# sra_board_2020.net
KiCad netlist of a schematic drawn in EAGLE
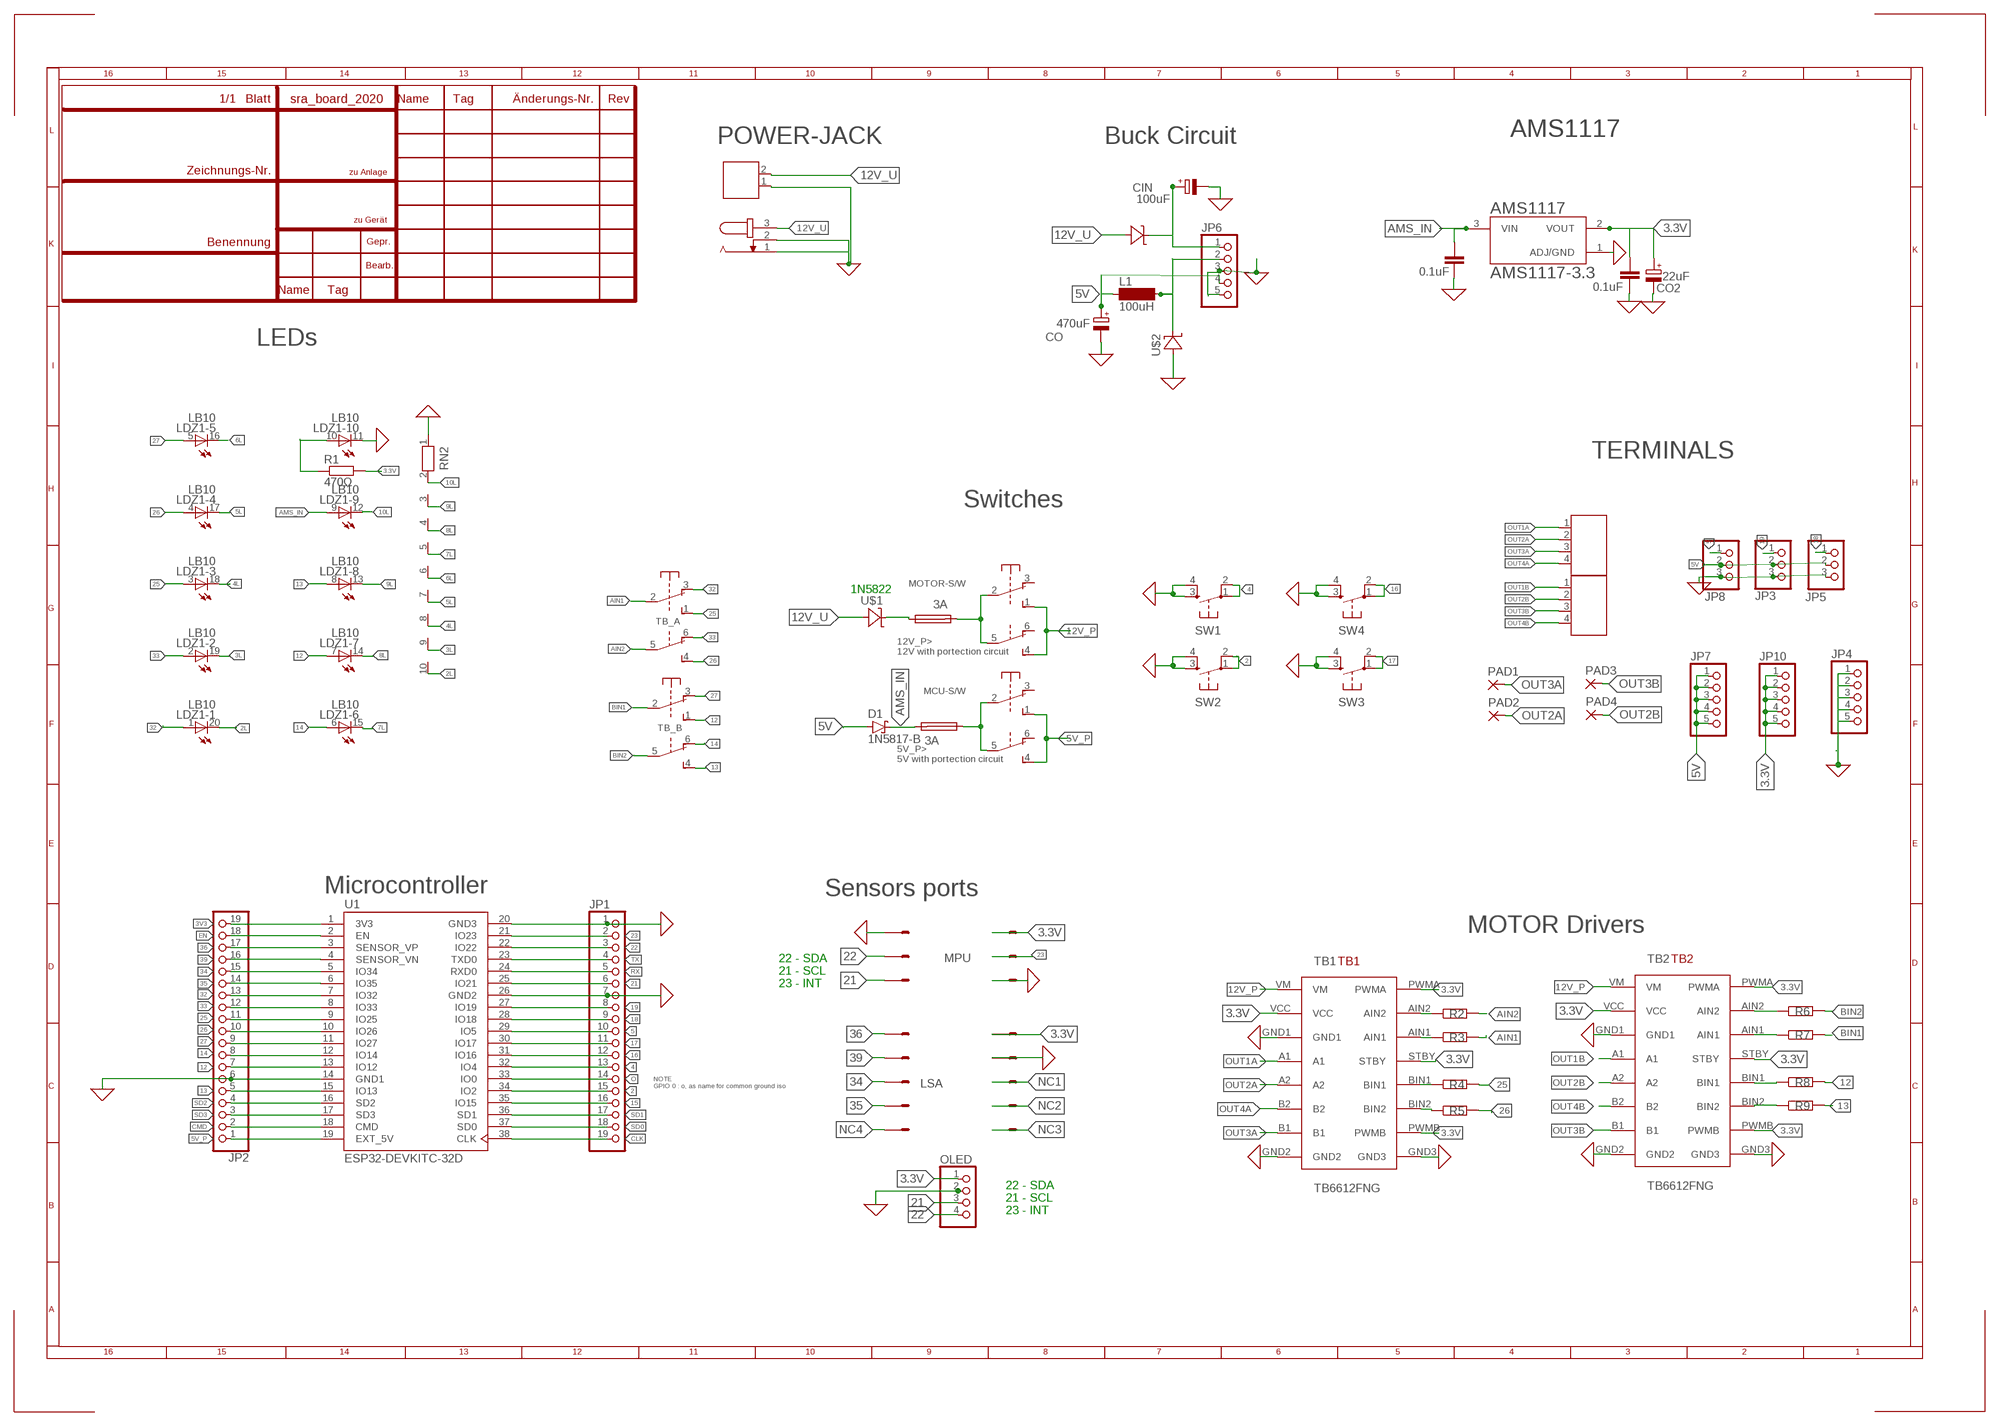
[diagram p0: schematic, sheet 1]

(export (version "E")
  (design (tool "Eeschema 10.0.6"))
  (components
    (comp (ref "12V")
      (value "691131710002")
      (footprint "eagle-import:691131710002")
      (libsource (lib "eagle-import") (part "691131710002"))
    )
    (comp (ref "AMS1117")
      (value "AMS1117-3.3")
      (footprint "eagle-import:SOT229P700X180-4N")
      (fields (field (name "MF") "Advanced Monolithic Systems"))
      (libsource (lib "eagle-import") (part "AMS1117-3.3"))
    )
    (comp (ref "CIN")
      (value "100uF")
      (footprint "eagle-import:E2,5-6")
      (libsource (lib "eagle-import") (part "CPOL-EUE2.5-6"))
    )
    (comp (ref "CIN1")
      (value "0.1uF")
      (footprint "eagle-import:C5B2.5")
      (libsource (lib "eagle-import") (part "C5/2.5"))
    )
    (comp (ref "CO")
      (value "470uF")
      (footprint "eagle-import:E3,5-10")
      (libsource (lib "eagle-import") (part "CPOL-EUE3.5-10"))
    )
    (comp (ref "CO1")
      (value "0.1uF")
      (footprint "eagle-import:C5B2.5")
      (libsource (lib "eagle-import") (part "C5/2.5"))
    )
    (comp (ref "CO2")
      (value "22uF")
      (footprint "eagle-import:E2,5-6")
      (libsource (lib "eagle-import") (part "CPOL-EUE2.5-6"))
    )
    (comp (ref "D1")
      (value "1N5817-B")
      (footprint "eagle-import:DO41-7.6")
      (libsource (lib "eagle-import") (part "1N5817-B"))
    )
    (comp (ref "F2")
      (value "3A")
      (footprint "eagle-import:SH25")
      (fields (field (name "MF") "SCHURTER") (field (name "MPN") "0031.8211"))
      (libsource (lib "eagle-import") (part "SH25"))
    )
    (comp (ref "F3")
      (value "3A")
      (footprint "eagle-import:SH25")
      (fields (field (name "MF") "SCHURTER") (field (name "MPN") "0031.8211"))
      (libsource (lib "eagle-import") (part "SH25"))
    )
    (comp (ref "J1")
      (value "691131710004")
      (footprint "eagle-import:691131710004")
      (libsource (lib "eagle-import") (part "691131710004"))
    )
    (comp (ref "J2")
      (value "691131710004")
      (footprint "eagle-import:691131710004")
      (libsource (lib "eagle-import") (part "691131710004"))
    )
    (comp (ref "JP1")
      (value "PINHD-1X19")
      (footprint "eagle-import:1X19")
      (libsource (lib "eagle-import") (part "PINHD-1X19"))
    )
    (comp (ref "JP2")
      (value "PINHD-1X19")
      (footprint "eagle-import:1X19")
      (libsource (lib "eagle-import") (part "PINHD-1X19"))
    )
    (comp (ref "JP3")
      (value "PINHD-1X3")
      (footprint "eagle-import:1X03")
      (libsource (lib "eagle-import") (part "PINHD-1X3"))
    )
    (comp (ref "JP4")
      (value "PINHD-1X5")
      (footprint "eagle-import:1X05")
      (libsource (lib "eagle-import") (part "pinhead_2_PINHD-1X5"))
    )
    (comp (ref "JP5")
      (value "PINHD-1X3")
      (footprint "eagle-import:1X03")
      (libsource (lib "eagle-import") (part "PINHD-1X3"))
    )
    (comp (ref "JP6")
      (value "PINHD-1X5")
      (footprint "eagle-import:1X05")
      (libsource (lib "eagle-import") (part "PINHD-1X5"))
    )
    (comp (ref "JP7")
      (value "PINHD-1X5")
      (footprint "eagle-import:1X05")
      (libsource (lib "eagle-import") (part "pinhead_2_PINHD-1X5"))
    )
    (comp (ref "JP8")
      (value "PINHD-1X3")
      (footprint "eagle-import:1X03")
      (libsource (lib "eagle-import") (part "PINHD-1X3"))
    )
    (comp (ref "JP10")
      (value "PINHD-1X5")
      (footprint "eagle-import:1X05")
      (libsource (lib "eagle-import") (part "pinhead_2_PINHD-1X5"))
    )
    (comp (ref "L1")
      (value "100uH")
      (footprint "eagle-import:SD12K100")
      (libsource (lib "eagle-import") (part "SD12K100"))
    )
    (comp (ref "LDZ1")
      (value "LB10")
      (footprint "eagle-import:LB10")
      (libsource (lib "eagle-import") (part "LB10"))
    )
    (comp (ref "LINE-SENSOR")
      (value "057-010-1")
      (footprint "eagle-import:057-010-1")
      (libsource (lib "eagle-import") (part "057-010-1"))
    )
    (comp (ref "MCU-S/W")
      (value "9077-2")
      (footprint "eagle-import:9077-2")
      (libsource (lib "eagle-import") (part "9077-2"))
    )
    (comp (ref "MOTOR-S/W")
      (value "9077-2")
      (footprint "eagle-import:9077-2")
      (libsource (lib "eagle-import") (part "9077-2"))
    )
    (comp (ref "OLED")
      (value "PINHD-1X4")
      (footprint "eagle-import:1X04")
      (libsource (lib "eagle-import") (part "PINHD-1X4"))
    )
    (comp (ref "PAD1")
      (value "SMD2")
      (footprint "eagle-import:SMD1,27-2,54")
      (libsource (lib "eagle-import") (part "SMD2"))
    )
    (comp (ref "PAD2")
      (value "SMD2")
      (footprint "eagle-import:SMD1,27-2,54")
      (libsource (lib "eagle-import") (part "SMD2"))
    )
    (comp (ref "PAD3")
      (value "SMD2")
      (footprint "eagle-import:SMD1,27-2,54")
      (libsource (lib "eagle-import") (part "SMD2"))
    )
    (comp (ref "PAD4")
      (value "SMD2")
      (footprint "eagle-import:SMD1,27-2,54")
      (libsource (lib "eagle-import") (part "SMD2"))
    )
    (comp (ref "POWER-JACK")
      (value "JACK-PLUG1")
      (footprint "eagle-import:SPC4078")
      (libsource (lib "eagle-import") (part "JACK-PLUG1"))
    )
    (comp (ref "R1")
      (value "470Ω")
      (footprint "eagle-import:0204_7")
      (libsource (lib "eagle-import") (part "R-EU_0204/7"))
    )
    (comp (ref "R2")
      (value "1KΩ")
      (footprint "eagle-import:0204_7")
      (libsource (lib "eagle-import") (part "R-EU_0204/7"))
    )
    (comp (ref "R3")
      (value "1KΩ")
      (footprint "eagle-import:0204_7")
      (libsource (lib "eagle-import") (part "R-EU_0204/7"))
    )
    (comp (ref "R4")
      (value "1KΩ")
      (footprint "eagle-import:0204_7")
      (libsource (lib "eagle-import") (part "R-EU_0204/7"))
    )
    (comp (ref "R5")
      (value "1KΩ")
      (footprint "eagle-import:0204_7")
      (libsource (lib "eagle-import") (part "R-EU_0204/7"))
    )
    (comp (ref "R6")
      (value "1KΩ")
      (footprint "eagle-import:0204_7")
      (libsource (lib "eagle-import") (part "R-EU_0204/7"))
    )
    (comp (ref "R7")
      (value "1KΩ")
      (footprint "eagle-import:0204_7")
      (libsource (lib "eagle-import") (part "R-EU_0204/7"))
    )
    (comp (ref "R8")
      (value "1KΩ")
      (footprint "eagle-import:0204_7")
      (libsource (lib "eagle-import") (part "R-EU_0204/7"))
    )
    (comp (ref "R9")
      (value "1KΩ")
      (footprint "eagle-import:0204_7")
      (libsource (lib "eagle-import") (part "R-EU_0204/7"))
    )
    (comp (ref "RN2")
      (value "RN09")
      (footprint "eagle-import:RN-10")
      (libsource (lib "eagle-import") (part "RN09"))
    )
    (comp (ref "SW1")
      (value "DTS-6")
      (footprint "eagle-import:DTS-6")
      (libsource (lib "eagle-import") (part "DTS-6"))
    )
    (comp (ref "SW2")
      (value "DTS-6")
      (footprint "eagle-import:DTS-6")
      (libsource (lib "eagle-import") (part "DTS-6"))
    )
    (comp (ref "SW3")
      (value "DTS-6")
      (footprint "eagle-import:DTS-6")
      (libsource (lib "eagle-import") (part "DTS-6"))
    )
    (comp (ref "SW4")
      (value "DTS-6")
      (footprint "eagle-import:DTS-6")
      (libsource (lib "eagle-import") (part "DTS-6"))
    )
    (comp (ref "TB1")
      (value "TB6612FNG")
      (footprint "eagle-import:TB6612FNG")
      (libsource (lib "eagle-import") (part "TB6612FNG"))
    )
    (comp (ref "TB2")
      (value "TB6612FNG")
      (footprint "eagle-import:TB6612FNG")
      (libsource (lib "eagle-import") (part "TB6612FNG"))
    )
    (comp (ref "TB_A")
      (value "9077-2")
      (footprint "eagle-import:9077-2")
      (libsource (lib "eagle-import") (part "9077-2"))
    )
    (comp (ref "TB_B")
      (value "9077-2")
      (footprint "eagle-import:9077-2")
      (libsource (lib "eagle-import") (part "9077-2"))
    )
    (comp (ref "U$1")
      (value "1N5399_SQUARE")
      (footprint "eagle-import:C2673")
      (libsource (lib "eagle-import") (part "1N5399_SQUARE"))
    )
    (comp (ref "U$2")
      (value "1N5399_SQUARE")
      (footprint "eagle-import:C2673")
      (libsource (lib "eagle-import") (part "1N5399_SQUARE"))
    )
    (comp (ref "U$3")
      (value "1N5399_ROUND")
      (footprint "eagle-import:D-10")
      (libsource (lib "eagle-import") (part "1N5399_ROUND"))
    )
    (comp (ref "U1")
      (value "ESP32-DEVKITC-32D")
      (footprint "eagle-import:MODULE_ESP32-DEVKITC-32D")
      (fields (field (name "MF") "Espressif Systems"))
      (libsource (lib "eagle-import") (part "ESP32-DEVKITC-32D"))
    )
    (comp (ref "X1")
      (value "057-006-1")
      (footprint "eagle-import:057-006-1")
      (libsource (lib "eagle-import") (part "057-006-1"))
    )
  )
  (nets
    (net (code "1") (name "2") (class "Default")
      (node (ref "JP1") (pin "15") (pinfunction "15_15") (pintype "passive"))
      (node (ref "SW2") (pin "1") (pinfunction "1_1") (pintype "passive"))
      (node (ref "SW2") (pin "2") (pinfunction "2_2") (pintype "passive"))
      (node (ref "U1") (pin "34") (pinfunction "IO2_34") (pintype "bidirectional"))
    )
    (net (code "2") (name "2L") (class "Default")
      (node (ref "LDZ1") (pin "20") (pinfunction "C_20") (pintype "passive"))
      (node (ref "RN2") (pin "10") (pinfunction "10_10") (pintype "passive"))
    )
    (net (code "3") (name "3.3V") (class "Default")
      (node (ref "AMS1117") (pin "2") (pinfunction "VOUT_2") (pintype "output"))
      (node (ref "CO1") (pin "2") (pinfunction "2_2") (pintype "passive"))
      (node (ref "CO2") (pin "+") (pinfunction "+_+") (pintype "passive"))
      (node (ref "JP10") (pin "1") (pinfunction "1_1") (pintype "passive"))
      (node (ref "JP10") (pin "2") (pinfunction "2_2") (pintype "passive"))
      (node (ref "JP10") (pin "3") (pinfunction "3_3") (pintype "passive"))
      (node (ref "JP10") (pin "4") (pinfunction "4_4") (pintype "passive"))
      (node (ref "JP10") (pin "5") (pinfunction "5_5") (pintype "passive"))
      (node (ref "LINE-SENSOR") (pin "2") (pinfunction "S_2") (pintype "passive"))
      (node (ref "OLED") (pin "1") (pinfunction "1_1") (pintype "passive"))
      (node (ref "R1") (pin "2") (pinfunction "2_2") (pintype "passive"))
      (node (ref "TB1") (pin "PWMA") (pinfunction "PWMA_PWMA") (pintype "bidirectional"))
      (node (ref "TB1") (pin "PWMB") (pinfunction "PWMB_PWMB") (pintype "bidirectional"))
      (node (ref "TB1") (pin "STBY") (pinfunction "STBY_STBY") (pintype "bidirectional"))
      (node (ref "TB1") (pin "VCC") (pinfunction "VCC_VCC") (pintype "bidirectional"))
      (node (ref "TB2") (pin "PWMA") (pinfunction "PWMA_PWMA") (pintype "bidirectional"))
      (node (ref "TB2") (pin "PWMB") (pinfunction "PWMB_PWMB") (pintype "bidirectional"))
      (node (ref "TB2") (pin "STBY") (pinfunction "STBY_STBY") (pintype "bidirectional"))
      (node (ref "TB2") (pin "VCC") (pinfunction "VCC_VCC") (pintype "bidirectional"))
      (node (ref "X1") (pin "2") (pinfunction "S_2") (pintype "passive"))
    )
    (net (code "4") (name "3L") (class "Default")
      (node (ref "LDZ1") (pin "19") (pinfunction "C_19") (pintype "passive"))
      (node (ref "RN2") (pin "9") (pinfunction "9_9") (pintype "passive"))
    )
    (net (code "5") (name "3V3") (class "Default")
      (node (ref "JP2") (pin "19") (pinfunction "19_19") (pintype "passive"))
      (node (ref "U1") (pin "1") (pinfunction "3V3_1") (pintype "power_in"))
    )
    (net (code "6") (name "4") (class "Default")
      (node (ref "JP1") (pin "13") (pinfunction "13_13") (pintype "passive"))
      (node (ref "SW1") (pin "1") (pinfunction "1_1") (pintype "passive"))
      (node (ref "SW1") (pin "2") (pinfunction "2_2") (pintype "passive"))
      (node (ref "U1") (pin "32") (pinfunction "IO4_32") (pintype "bidirectional"))
    )
    (net (code "7") (name "4L") (class "Default")
      (node (ref "LDZ1") (pin "18") (pinfunction "C_18") (pintype "passive"))
      (node (ref "RN2") (pin "8") (pinfunction "8_8") (pintype "passive"))
    )
    (net (code "8") (name "5") (class "Default")
      (node (ref "JP1") (pin "10") (pinfunction "10_10") (pintype "passive"))
      (node (ref "JP8") (pin "1") (pinfunction "1_1") (pintype "passive"))
      (node (ref "U1") (pin "29") (pinfunction "IO5_29") (pintype "bidirectional"))
    )
    (net (code "9") (name "5L") (class "Default")
      (node (ref "LDZ1") (pin "17") (pinfunction "C_17") (pintype "passive"))
      (node (ref "RN2") (pin "7") (pinfunction "7_7") (pintype "passive"))
    )
    (net (code "10") (name "5V") (class "Default")
      (node (ref "CO") (pin "+") (pinfunction "+_+") (pintype "passive"))
      (node (ref "D1") (pin "A") (pinfunction "A_A") (pintype "passive"))
      (node (ref "JP3") (pin "2") (pinfunction "2_2") (pintype "passive"))
      (node (ref "JP5") (pin "2") (pinfunction "2_2") (pintype "passive"))
      (node (ref "JP6") (pin "4") (pinfunction "4_4") (pintype "passive"))
      (node (ref "JP7") (pin "1") (pinfunction "1_1") (pintype "passive"))
      (node (ref "JP7") (pin "2") (pinfunction "2_2") (pintype "passive"))
      (node (ref "JP7") (pin "3") (pinfunction "3_3") (pintype "passive"))
      (node (ref "JP7") (pin "4") (pinfunction "4_4") (pintype "passive"))
      (node (ref "JP7") (pin "5") (pinfunction "5_5") (pintype "passive"))
      (node (ref "JP8") (pin "2") (pinfunction "2_2") (pintype "passive"))
      (node (ref "L1") (pin "1") (pinfunction "1_1") (pintype "passive"))
    )
    (net (code "11") (name "5V_P") (class "Default")
      (node (ref "JP2") (pin "1") (pinfunction "1_1") (pintype "passive"))
      (node (ref "MCU-S/W") (pin "1") (pinfunction "S_1") (pintype "passive"))
      (node (ref "MCU-S/W") (pin "4") (pinfunction "S_4") (pintype "passive"))
      (node (ref "U1") (pin "19") (pinfunction "EXT_5V_19") (pintype "power_in"))
    )
    (net (code "12") (name "6L") (class "Default")
      (node (ref "LDZ1") (pin "16") (pinfunction "C_16") (pintype "passive"))
      (node (ref "RN2") (pin "6") (pinfunction "6_6") (pintype "passive"))
    )
    (net (code "13") (name "7L") (class "Default")
      (node (ref "LDZ1") (pin "15") (pinfunction "C_15") (pintype "passive"))
      (node (ref "RN2") (pin "5") (pinfunction "5_5") (pintype "passive"))
    )
    (net (code "14") (name "8L") (class "Default")
      (node (ref "LDZ1") (pin "14") (pinfunction "C_14") (pintype "passive"))
      (node (ref "RN2") (pin "4") (pinfunction "4_4") (pintype "passive"))
    )
    (net (code "15") (name "9L") (class "Default")
      (node (ref "LDZ1") (pin "13") (pinfunction "C_13") (pintype "passive"))
      (node (ref "RN2") (pin "3") (pinfunction "3_3") (pintype "passive"))
    )
    (net (code "16") (name "10L") (class "Default")
      (node (ref "LDZ1") (pin "12") (pinfunction "C_12") (pintype "passive"))
      (node (ref "RN2") (pin "2") (pinfunction "2_2") (pintype "passive"))
    )
    (net (code "17") (name "12") (class "Default")
      (node (ref "JP2") (pin "7") (pinfunction "7_7") (pintype "passive"))
      (node (ref "LDZ1") (pin "7") (pinfunction "A_7") (pintype "passive"))
      (node (ref "R8") (pin "2") (pinfunction "2_2") (pintype "passive"))
      (node (ref "TB_B") (pin "1") (pinfunction "S_1") (pintype "passive"))
      (node (ref "U1") (pin "13") (pinfunction "IO12_13") (pintype "bidirectional"))
    )
    (net (code "18") (name "12V_P") (class "Default")
      (node (ref "MOTOR-S/W") (pin "1") (pinfunction "S_1") (pintype "passive"))
      (node (ref "MOTOR-S/W") (pin "4") (pinfunction "S_4") (pintype "passive"))
      (node (ref "TB1") (pin "VM") (pinfunction "VM_VM") (pintype "bidirectional"))
      (node (ref "TB2") (pin "VM") (pinfunction "VM_VM") (pintype "bidirectional"))
    )
    (net (code "19") (name "12V_U") (class "Default")
      (node (ref "12V") (pin "2") (pinfunction "2_2") (pintype "passive"))
      (node (ref "POWER-JACK") (pin "3") (pinfunction "3_3") (pintype "passive"))
      (node (ref "U$1") (pin "A") (pinfunction "A_A") (pintype "passive"))
      (node (ref "U$3") (pin "A") (pinfunction "A_A") (pintype "passive"))
    )
    (net (code "20") (name "13") (class "Default")
      (node (ref "JP2") (pin "5") (pinfunction "5_5") (pintype "passive"))
      (node (ref "LDZ1") (pin "8") (pinfunction "A_8") (pintype "passive"))
      (node (ref "R9") (pin "2") (pinfunction "2_2") (pintype "passive"))
      (node (ref "TB_B") (pin "4") (pinfunction "S_4") (pintype "passive"))
      (node (ref "U1") (pin "15") (pinfunction "IO13_15") (pintype "bidirectional"))
    )
    (net (code "21") (name "14") (class "Default")
      (node (ref "JP2") (pin "8") (pinfunction "8_8") (pintype "passive"))
      (node (ref "LDZ1") (pin "6") (pinfunction "A_6") (pintype "passive"))
      (node (ref "TB_B") (pin "6") (pinfunction "O_6") (pintype "passive"))
      (node (ref "U1") (pin "12") (pinfunction "IO14_12") (pintype "bidirectional"))
    )
    (net (code "22") (name "15") (class "Default")
      (node (ref "JP1") (pin "16") (pinfunction "16_16") (pintype "passive"))
      (node (ref "U1") (pin "35") (pinfunction "IO15_35") (pintype "bidirectional"))
    )
    (net (code "23") (name "16") (class "Default")
      (node (ref "JP1") (pin "12") (pinfunction "12_12") (pintype "passive"))
      (node (ref "SW4") (pin "1") (pinfunction "1_1") (pintype "passive"))
      (node (ref "SW4") (pin "2") (pinfunction "2_2") (pintype "passive"))
      (node (ref "U1") (pin "31") (pinfunction "IO16_31") (pintype "bidirectional"))
    )
    (net (code "24") (name "17") (class "Default")
      (node (ref "JP1") (pin "11") (pinfunction "11_11") (pintype "passive"))
      (node (ref "SW3") (pin "1") (pinfunction "1_1") (pintype "passive"))
      (node (ref "SW3") (pin "2") (pinfunction "2_2") (pintype "passive"))
      (node (ref "U1") (pin "30") (pinfunction "IO17_30") (pintype "bidirectional"))
    )
    (net (code "25") (name "18") (class "Default")
      (node (ref "JP1") (pin "9") (pinfunction "9_9") (pintype "passive"))
      (node (ref "JP5") (pin "1") (pinfunction "1_1") (pintype "passive"))
      (node (ref "U1") (pin "28") (pinfunction "IO18_28") (pintype "bidirectional"))
    )
    (net (code "26") (name "19") (class "Default")
      (node (ref "JP1") (pin "8") (pinfunction "8_8") (pintype "passive"))
      (node (ref "JP3") (pin "1") (pinfunction "1_1") (pintype "passive"))
      (node (ref "U1") (pin "27") (pinfunction "IO19_27") (pintype "bidirectional"))
    )
    (net (code "27") (name "21") (class "Default")
      (node (ref "JP1") (pin "6") (pinfunction "6_6") (pintype "passive"))
      (node (ref "OLED") (pin "3") (pinfunction "3_3") (pintype "passive"))
      (node (ref "U1") (pin "25") (pinfunction "IO21_25") (pintype "bidirectional"))
      (node (ref "X1") (pin "5") (pinfunction "S_5") (pintype "passive"))
    )
    (net (code "28") (name "22") (class "Default")
      (node (ref "JP1") (pin "3") (pinfunction "3_3") (pintype "passive"))
      (node (ref "OLED") (pin "4") (pinfunction "4_4") (pintype "passive"))
      (node (ref "U1") (pin "22") (pinfunction "IO22_22") (pintype "bidirectional"))
      (node (ref "X1") (pin "3") (pinfunction "S_3") (pintype "passive"))
    )
    (net (code "29") (name "23") (class "Default")
      (node (ref "JP1") (pin "2") (pinfunction "2_2") (pintype "passive"))
      (node (ref "U1") (pin "21") (pinfunction "IO23_21") (pintype "bidirectional"))
      (node (ref "X1") (pin "4") (pinfunction "S_4") (pintype "passive"))
    )
    (net (code "30") (name "25") (class "Default")
      (node (ref "JP2") (pin "11") (pinfunction "11_11") (pintype "passive"))
      (node (ref "LDZ1") (pin "3") (pinfunction "A_3") (pintype "passive"))
      (node (ref "R4") (pin "2") (pinfunction "2_2") (pintype "passive"))
      (node (ref "TB_A") (pin "1") (pinfunction "S_1") (pintype "passive"))
      (node (ref "U1") (pin "9") (pinfunction "IO25_9") (pintype "bidirectional"))
    )
    (net (code "31") (name "26") (class "Default")
      (node (ref "JP2") (pin "10") (pinfunction "10_10") (pintype "passive"))
      (node (ref "LDZ1") (pin "4") (pinfunction "A_4") (pintype "passive"))
      (node (ref "R5") (pin "2") (pinfunction "2_2") (pintype "passive"))
      (node (ref "TB_A") (pin "4") (pinfunction "S_4") (pintype "passive"))
      (node (ref "U1") (pin "10") (pinfunction "IO26_10") (pintype "bidirectional"))
    )
    (net (code "32") (name "27") (class "Default")
      (node (ref "JP2") (pin "9") (pinfunction "9_9") (pintype "passive"))
      (node (ref "LDZ1") (pin "5") (pinfunction "A_5") (pintype "passive"))
      (node (ref "TB_B") (pin "3") (pinfunction "O_3") (pintype "passive"))
      (node (ref "U1") (pin "11") (pinfunction "IO27_11") (pintype "bidirectional"))
    )
    (net (code "33") (name "32") (class "Default")
      (node (ref "JP2") (pin "13") (pinfunction "13_13") (pintype "passive"))
      (node (ref "LDZ1") (pin "1") (pinfunction "A_1") (pintype "passive"))
      (node (ref "TB_A") (pin "3") (pinfunction "O_3") (pintype "passive"))
      (node (ref "U1") (pin "7") (pinfunction "IO32_7") (pintype "bidirectional"))
    )
    (net (code "34") (name "33") (class "Default")
      (node (ref "JP2") (pin "12") (pinfunction "12_12") (pintype "passive"))
      (node (ref "LDZ1") (pin "2") (pinfunction "A_2") (pintype "passive"))
      (node (ref "TB_A") (pin "6") (pinfunction "O_6") (pintype "passive"))
      (node (ref "U1") (pin "8") (pinfunction "IO33_8") (pintype "bidirectional"))
    )
    (net (code "35") (name "34") (class "Default")
      (node (ref "JP2") (pin "15") (pinfunction "15_15") (pintype "passive"))
      (node (ref "LINE-SENSOR") (pin "5") (pinfunction "S_5") (pintype "passive"))
      (node (ref "U1") (pin "5") (pinfunction "IO34_5") (pintype "bidirectional"))
    )
    (net (code "36") (name "35") (class "Default")
      (node (ref "JP2") (pin "14") (pinfunction "14_14") (pintype "passive"))
      (node (ref "LINE-SENSOR") (pin "7") (pinfunction "S_7") (pintype "passive"))
      (node (ref "U1") (pin "6") (pinfunction "IO35_6") (pintype "bidirectional"))
    )
    (net (code "37") (name "36") (class "Default")
      (node (ref "JP2") (pin "17") (pinfunction "17_17") (pintype "passive"))
      (node (ref "LINE-SENSOR") (pin "1") (pinfunction "S_1") (pintype "passive"))
      (node (ref "U1") (pin "3") (pinfunction "SENSOR_VP_3") (pintype "input"))
    )
    (net (code "38") (name "39") (class "Default")
      (node (ref "JP2") (pin "16") (pinfunction "16_16") (pintype "passive"))
      (node (ref "LINE-SENSOR") (pin "3") (pinfunction "S_3") (pintype "passive"))
      (node (ref "U1") (pin "4") (pinfunction "SENSOR_VN_4") (pintype "input"))
    )
    (net (code "39") (name "AIN1") (class "Default")
      (node (ref "R3") (pin "2") (pinfunction "2_2") (pintype "passive"))
      (node (ref "TB_A") (pin "2") (pinfunction "P_2") (pintype "passive"))
    )
    (net (code "40") (name "AIN2") (class "Default")
      (node (ref "R2") (pin "2") (pinfunction "2_2") (pintype "passive"))
      (node (ref "TB_A") (pin "5") (pinfunction "P_5") (pintype "passive"))
    )
    (net (code "41") (name "AMS_IN") (class "Default")
      (node (ref "AMS1117") (pin "3") (pinfunction "VIN_3") (pintype "input"))
      (node (ref "CIN1") (pin "2") (pinfunction "2_2") (pintype "passive"))
      (node (ref "D1") (pin "C") (pinfunction "C_C") (pintype "passive"))
      (node (ref "F2") (pin "2") (pinfunction "2_2") (pintype "passive"))
      (node (ref "LDZ1") (pin "9") (pinfunction "A_9") (pintype "passive"))
    )
    (net (code "42") (name "BIN1") (class "Default")
      (node (ref "R7") (pin "2") (pinfunction "2_2") (pintype "passive"))
      (node (ref "TB_B") (pin "2") (pinfunction "P_2") (pintype "passive"))
    )
    (net (code "43") (name "BIN2") (class "Default")
      (node (ref "R6") (pin "2") (pinfunction "2_2") (pintype "passive"))
      (node (ref "TB_B") (pin "5") (pinfunction "P_5") (pintype "passive"))
    )
    (net (code "44") (name "CLK") (class "Default")
      (node (ref "JP1") (pin "19") (pinfunction "19_19") (pintype "passive"))
      (node (ref "U1") (pin "38") (pinfunction "CLK_38") (pintype "input"))
    )
    (net (code "45") (name "CMD") (class "Default")
      (node (ref "JP2") (pin "2") (pinfunction "2_2") (pintype "passive"))
      (node (ref "U1") (pin "18") (pinfunction "CMD_18") (pintype "bidirectional"))
    )
    (net (code "46") (name "EN") (class "Default")
      (node (ref "JP2") (pin "18") (pinfunction "18_18") (pintype "passive"))
      (node (ref "U1") (pin "2") (pinfunction "EN_2") (pintype "input"))
    )
    (net (code "47") (name "GND") (class "Default")
      (node (ref "12V") (pin "1") (pinfunction "1_1") (pintype "passive"))
      (node (ref "AMS1117") (pin "1") (pinfunction "ADJ/GND_1") (pintype "power_in"))
      (node (ref "CIN") (pin "-") (pinfunction "-_-") (pintype "passive"))
      (node (ref "CIN1") (pin "1") (pinfunction "1_1") (pintype "passive"))
      (node (ref "CO") (pin "-") (pinfunction "-_-") (pintype "passive"))
      (node (ref "CO1") (pin "1") (pinfunction "1_1") (pintype "passive"))
      (node (ref "CO2") (pin "-") (pinfunction "-_-") (pintype "passive"))
      (node (ref "JP1") (pin "1") (pinfunction "1_1") (pintype "passive"))
      (node (ref "JP1") (pin "7") (pinfunction "7_7") (pintype "passive"))
      (node (ref "JP2") (pin "6") (pinfunction "6_6") (pintype "passive"))
      (node (ref "JP3") (pin "3") (pinfunction "3_3") (pintype "passive"))
      (node (ref "JP4") (pin "1") (pinfunction "1_1") (pintype "passive"))
      (node (ref "JP4") (pin "2") (pinfunction "2_2") (pintype "passive"))
      (node (ref "JP4") (pin "3") (pinfunction "3_3") (pintype "passive"))
      (node (ref "JP4") (pin "4") (pinfunction "4_4") (pintype "passive"))
      (node (ref "JP4") (pin "5") (pinfunction "5_5") (pintype "passive"))
      (node (ref "JP5") (pin "3") (pinfunction "3_3") (pintype "passive"))
      (node (ref "JP6") (pin "3") (pinfunction "3_3") (pintype "passive"))
      (node (ref "JP6") (pin "5") (pinfunction "5_5") (pintype "passive"))
      (node (ref "JP8") (pin "3") (pinfunction "3_3") (pintype "passive"))
      (node (ref "LDZ1") (pin "11") (pinfunction "C_11") (pintype "passive"))
      (node (ref "LINE-SENSOR") (pin "4") (pinfunction "S_4") (pintype "passive"))
      (node (ref "OLED") (pin "2") (pinfunction "2_2") (pintype "passive"))
      (node (ref "POWER-JACK") (pin "1") (pinfunction "1_1") (pintype "passive"))
      (node (ref "POWER-JACK") (pin "2") (pinfunction "2_2") (pintype "passive"))
      (node (ref "RN2") (pin "1") (pinfunction "1_1") (pintype "passive"))
      (node (ref "SW1") (pin "3") (pinfunction "3_3") (pintype "passive"))
      (node (ref "SW1") (pin "4") (pinfunction "4_4") (pintype "passive"))
      (node (ref "SW2") (pin "3") (pinfunction "3_3") (pintype "passive"))
      (node (ref "SW2") (pin "4") (pinfunction "4_4") (pintype "passive"))
      (node (ref "SW3") (pin "3") (pinfunction "3_3") (pintype "passive"))
      (node (ref "SW3") (pin "4") (pinfunction "4_4") (pintype "passive"))
      (node (ref "SW4") (pin "3") (pinfunction "3_3") (pintype "passive"))
      (node (ref "SW4") (pin "4") (pinfunction "4_4") (pintype "passive"))
      (node (ref "TB1") (pin "GND1") (pinfunction "GND1_GND1") (pintype "bidirectional"))
      (node (ref "TB1") (pin "GND2") (pinfunction "GND2_GND2") (pintype "bidirectional"))
      (node (ref "TB1") (pin "GND3") (pinfunction "GND3_GND3") (pintype "bidirectional"))
      (node (ref "TB2") (pin "GND1") (pinfunction "GND1_GND1") (pintype "bidirectional"))
      (node (ref "TB2") (pin "GND2") (pinfunction "GND2_GND2") (pintype "bidirectional"))
      (node (ref "TB2") (pin "GND3") (pinfunction "GND3_GND3") (pintype "bidirectional"))
      (node (ref "U$2") (pin "A") (pinfunction "A_A") (pintype "passive"))
      (node (ref "U1") (pin "14") (pinfunction "GND1_14") (pintype "power_in"))
      (node (ref "U1") (pin "20") (pinfunction "GND3_20") (pintype "power_in"))
      (node (ref "U1") (pin "26") (pinfunction "GND2_26") (pintype "power_in"))
      (node (ref "X1") (pin "1") (pinfunction "S_1") (pintype "passive"))
      (node (ref "X1") (pin "6") (pinfunction "S_6") (pintype "passive"))
    )
    (net (code "48") (name "NC1") (class "Default")
      (node (ref "LINE-SENSOR") (pin "6") (pinfunction "S_6") (pintype "passive"))
    )
    (net (code "49") (name "NC2") (class "Default")
      (node (ref "LINE-SENSOR") (pin "8") (pinfunction "S_8") (pintype "passive"))
    )
    (net (code "50") (name "NC3") (class "Default")
      (node (ref "LINE-SENSOR") (pin "10") (pinfunction "S_10") (pintype "passive"))
    )
    (net (code "51") (name "NC4") (class "Default")
      (node (ref "LINE-SENSOR") (pin "9") (pinfunction "S_9") (pintype "passive"))
    )
    (net (code "52") (name "Net-(CIN-Pad+)") (class "Default")
      (node (ref "CIN") (pin "+") (pinfunction "+_+") (pintype "passive"))
      (node (ref "JP6") (pin "1") (pinfunction "1_1") (pintype "passive"))
      (node (ref "U$3") (pin "C") (pinfunction "C_C") (pintype "passive"))
    )
    (net (code "53") (name "Net-(F3-Pad1)") (class "Default")
      (node (ref "F3") (pin "1") (pinfunction "1_1") (pintype "passive"))
      (node (ref "U$1") (pin "C") (pinfunction "C_C") (pintype "passive"))
    )
    (net (code "54") (name "Net-(JP6-Pad2)") (class "Default")
      (node (ref "JP6") (pin "2") (pinfunction "2_2") (pintype "passive"))
      (node (ref "L1") (pin "2") (pinfunction "2_2") (pintype "passive"))
      (node (ref "U$2") (pin "C") (pinfunction "C_C") (pintype "passive"))
    )
    (net (code "55") (name "Net-(LDZ1B-A)") (class "Default")
      (node (ref "LDZ1") (pin "10") (pinfunction "A_10") (pintype "passive"))
      (node (ref "R1") (pin "1") (pinfunction "1_1") (pintype "passive"))
    )
    (net (code "56") (name "Net-(MCU-S/WA-P)") (class "Default")
      (node (ref "F2") (pin "1") (pinfunction "1_1") (pintype "passive"))
      (node (ref "MCU-S/W") (pin "2") (pinfunction "P_2") (pintype "passive"))
      (node (ref "MCU-S/W") (pin "5") (pinfunction "P_5") (pintype "passive"))
    )
    (net (code "57") (name "Net-(MOTOR-S/WA-P)") (class "Default")
      (node (ref "F3") (pin "2") (pinfunction "2_2") (pintype "passive"))
      (node (ref "MOTOR-S/W") (pin "2") (pinfunction "P_2") (pintype "passive"))
      (node (ref "MOTOR-S/W") (pin "5") (pinfunction "P_5") (pintype "passive"))
    )
    (net (code "58") (name "Net-(R2-Pad1)") (class "Default")
      (node (ref "R2") (pin "1") (pinfunction "1_1") (pintype "passive"))
      (node (ref "TB1") (pin "AIN2") (pinfunction "AIN2_AIN2") (pintype "bidirectional"))
    )
    (net (code "59") (name "Net-(R3-Pad1)") (class "Default")
      (node (ref "R3") (pin "1") (pinfunction "1_1") (pintype "passive"))
      (node (ref "TB1") (pin "AIN1") (pinfunction "AIN1_AIN1") (pintype "bidirectional"))
    )
    (net (code "60") (name "Net-(R4-Pad1)") (class "Default")
      (node (ref "R4") (pin "1") (pinfunction "1_1") (pintype "passive"))
      (node (ref "TB1") (pin "BIN1") (pinfunction "BIN1_BIN1") (pintype "bidirectional"))
    )
    (net (code "61") (name "Net-(R5-Pad1)") (class "Default")
      (node (ref "R5") (pin "1") (pinfunction "1_1") (pintype "passive"))
      (node (ref "TB1") (pin "BIN2") (pinfunction "BIN2_BIN2") (pintype "bidirectional"))
    )
    (net (code "62") (name "Net-(R6-Pad1)") (class "Default")
      (node (ref "R6") (pin "1") (pinfunction "1_1") (pintype "passive"))
      (node (ref "TB2") (pin "AIN2") (pinfunction "AIN2_AIN2") (pintype "bidirectional"))
    )
    (net (code "63") (name "Net-(R7-Pad1)") (class "Default")
      (node (ref "R7") (pin "1") (pinfunction "1_1") (pintype "passive"))
      (node (ref "TB2") (pin "AIN1") (pinfunction "AIN1_AIN1") (pintype "bidirectional"))
    )
    (net (code "64") (name "Net-(R8-Pad1)") (class "Default")
      (node (ref "R8") (pin "1") (pinfunction "1_1") (pintype "passive"))
      (node (ref "TB2") (pin "BIN1") (pinfunction "BIN1_BIN1") (pintype "bidirectional"))
    )
    (net (code "65") (name "Net-(R9-Pad1)") (class "Default")
      (node (ref "R9") (pin "1") (pinfunction "1_1") (pintype "passive"))
      (node (ref "TB2") (pin "BIN2") (pinfunction "BIN2_BIN2") (pintype "bidirectional"))
    )
    (net (code "66") (name "O") (class "Default")
      (node (ref "JP1") (pin "14") (pinfunction "14_14") (pintype "passive"))
      (node (ref "U1") (pin "33") (pinfunction "IO0_33") (pintype "bidirectional"))
    )
    (net (code "67") (name "OUT1A") (class "Default")
      (node (ref "J1") (pin "1") (pinfunction "1_1") (pintype "passive"))
      (node (ref "TB1") (pin "A1") (pinfunction "A1_A1") (pintype "bidirectional"))
    )
    (net (code "68") (name "OUT1B") (class "Default")
      (node (ref "J2") (pin "1") (pinfunction "1_1") (pintype "passive"))
      (node (ref "TB2") (pin "A1") (pinfunction "A1_A1") (pintype "bidirectional"))
    )
    (net (code "69") (name "OUT2A") (class "Default")
      (node (ref "J1") (pin "2") (pinfunction "2_2") (pintype "passive"))
      (node (ref "PAD2") (pin "1") (pinfunction "P_1") (pintype "passive"))
      (node (ref "TB1") (pin "A2") (pinfunction "A2_A2") (pintype "bidirectional"))
    )
    (net (code "70") (name "OUT2B") (class "Default")
      (node (ref "J2") (pin "2") (pinfunction "2_2") (pintype "passive"))
      (node (ref "PAD4") (pin "1") (pinfunction "P_1") (pintype "passive"))
      (node (ref "TB2") (pin "A2") (pinfunction "A2_A2") (pintype "bidirectional"))
    )
    (net (code "71") (name "OUT3A") (class "Default")
      (node (ref "J1") (pin "3") (pinfunction "3_3") (pintype "passive"))
      (node (ref "PAD1") (pin "1") (pinfunction "P_1") (pintype "passive"))
      (node (ref "TB1") (pin "B1") (pinfunction "B1_B1") (pintype "bidirectional"))
    )
    (net (code "72") (name "OUT3B") (class "Default")
      (node (ref "J2") (pin "3") (pinfunction "3_3") (pintype "passive"))
      (node (ref "PAD3") (pin "1") (pinfunction "P_1") (pintype "passive"))
      (node (ref "TB2") (pin "B1") (pinfunction "B1_B1") (pintype "bidirectional"))
    )
    (net (code "73") (name "OUT4A") (class "Default")
      (node (ref "J1") (pin "4") (pinfunction "4_4") (pintype "passive"))
      (node (ref "TB1") (pin "B2") (pinfunction "B2_B2") (pintype "bidirectional"))
    )
    (net (code "74") (name "OUT4B") (class "Default")
      (node (ref "J2") (pin "4") (pinfunction "4_4") (pintype "passive"))
      (node (ref "TB2") (pin "B2") (pinfunction "B2_B2") (pintype "bidirectional"))
    )
    (net (code "75") (name "RX") (class "Default")
      (node (ref "JP1") (pin "5") (pinfunction "5_5") (pintype "passive"))
      (node (ref "U1") (pin "24") (pinfunction "RXD0_24") (pintype "input"))
    )
    (net (code "76") (name "SD0") (class "Default")
      (node (ref "JP1") (pin "18") (pinfunction "18_18") (pintype "passive"))
      (node (ref "U1") (pin "37") (pinfunction "SD0_37") (pintype "bidirectional"))
    )
    (net (code "77") (name "SD1") (class "Default")
      (node (ref "JP1") (pin "17") (pinfunction "17_17") (pintype "passive"))
      (node (ref "U1") (pin "36") (pinfunction "SD1_36") (pintype "bidirectional"))
    )
    (net (code "78") (name "SD2") (class "Default")
      (node (ref "JP2") (pin "4") (pinfunction "4_4") (pintype "passive"))
      (node (ref "U1") (pin "16") (pinfunction "SD2_16") (pintype "bidirectional"))
    )
    (net (code "79") (name "SD3") (class "Default")
      (node (ref "JP2") (pin "3") (pinfunction "3_3") (pintype "passive"))
      (node (ref "U1") (pin "17") (pinfunction "SD3_17") (pintype "bidirectional"))
    )
    (net (code "80") (name "TX") (class "Default")
      (node (ref "JP1") (pin "4") (pinfunction "4_4") (pintype "passive"))
      (node (ref "U1") (pin "23") (pinfunction "TXD0_23") (pintype "output"))
    )
    (net (code "81") (name "unconnected-(MCU-S/WA-O-Pad3)") (class "Default")
      (node (ref "MCU-S/W") (pin "3") (pinfunction "O_3") (pintype "passive"))
    )
    (net (code "82") (name "unconnected-(MCU-S/WB-O-Pad6)") (class "Default")
      (node (ref "MCU-S/W") (pin "6") (pinfunction "O_6") (pintype "passive"))
    )
    (net (code "83") (name "unconnected-(MOTOR-S/WA-O-Pad3)") (class "Default")
      (node (ref "MOTOR-S/W") (pin "3") (pinfunction "O_3") (pintype "passive"))
    )
    (net (code "84") (name "unconnected-(MOTOR-S/WB-O-Pad6)") (class "Default")
      (node (ref "MOTOR-S/W") (pin "6") (pinfunction "O_6") (pintype "passive"))
    )
  )
)
